# HV_PDU.net
KiCad netlist of a schematic drawn in Altium Designer
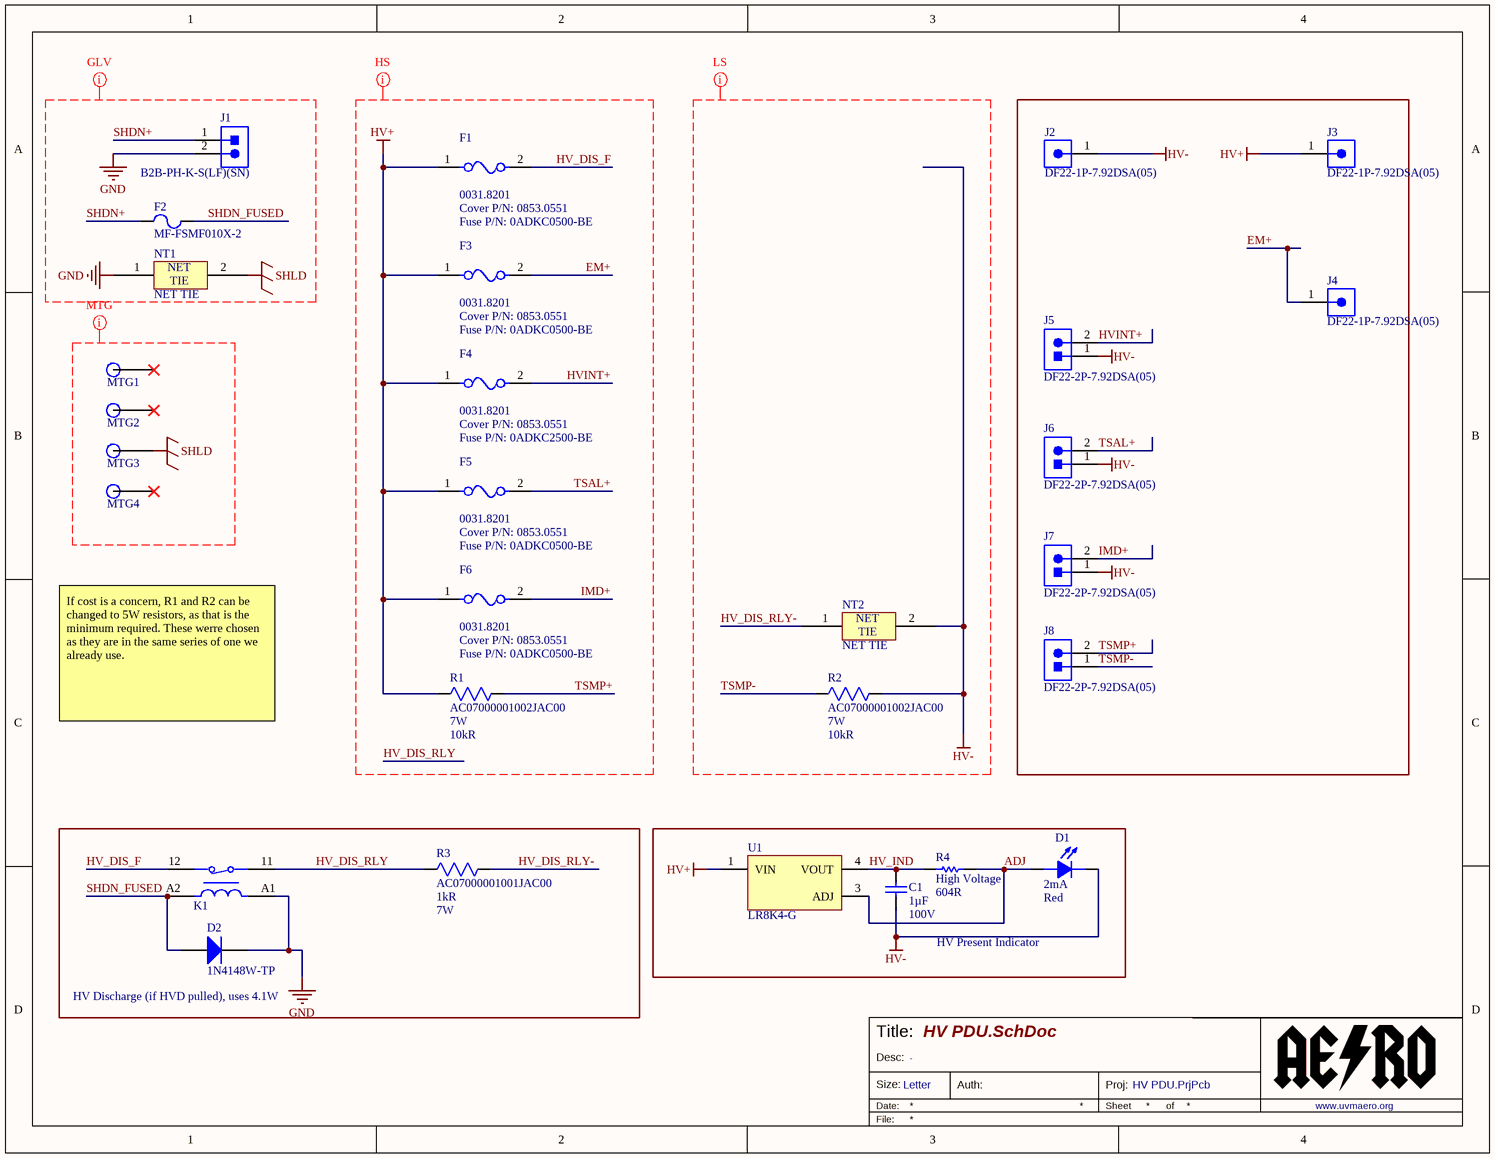
[diagram p0: HV PDU.SchDoc]

(export (version "E")
  (design (tool "Eeschema 10.0.6"))
  (components
    (comp (ref "C1")
      (value "C2012X7S2A105K125AB")
      (footprint "CAPC2013X145X20ML20")
      (description "Chip Capacitor, 1 uF, +/- 10%, 100 V, -55 to 125 degC, 0805 (2012 Metric), RoHS, Tape and Reel")
      (fields
        (field (name "PCN PART NUMBER") "MLCCPartNumberChange30/Nov/2012")
        (field (name "MANUFACTURER") "TDK")
        (field (name "CAPACITANCE") "1µF")
        (field (name "VOLTAGE - RATED") "100V")
      )
      (libsource (lib "AERO Parts") (part "C2012X7S2A105K125AB"))
    )
    (comp (ref "D1")
      (value "WP7113LSECK/J3")
      (footprint "LED_5MM")
      (description "Red 625nm LED Indication - Discrete 1.8V Radial")
      (fields
        (field (name "MANUFACTURER") "Kingbright")
        (field (name "TEST CURRENT") "2mA")
        (field (name "COLOR") "Red")
      )
      (libsource (lib "AERO Parts") (part "WP7113LSECK/J3"))
    )
    (comp (ref "D2")
      (value "1N4148W-TP")
      (footprint "MCC-SOD123_V")
      (description "High Speed Switching Diode, 400 mW, 150 mA, -65 to 150 degC, 2-Pin SOD123, RoHS, Tape and Reel")
      (fields (field (name "MANUFACTURER") "Micro Commercial Components"))
      (libsource (lib "Altium Content Vault") (part "D-AK-2"))
    )
    (comp (ref "F1")
      (value "0031.8201")
      (footprint "Schurter_0031.8201_ASM")
      (description "Fuse Block 10A 500V 1 Circuit Cartridge Through Hole")
      (fields
        (field (name "MANUFACTURER") "Schurter")
        (field (name "MANUFACTURER PART NUMBER") "00318201")
        (field (name "COVER P/N") "0853.0551")
        (field (name "FUSE P/N") "0ADKC0500-BE")
      )
      (libsource (lib "AERO Parts") (part "0031.8201"))
    )
    (comp (ref "F2")
      (value "MF-FSMF010X-2")
      (footprint "MF-FSMF")
      (description "Polymeric PTC Resettable Fuse 15V 100mA Ih Surface Mount 0603 (1608 Metric), Concave")
      (libsource (lib "AERO Parts") (part "MF-FSMF010X-2"))
    )
    (comp (ref "F3")
      (value "0031.8201")
      (footprint "Schurter_0031.8201_ASM")
      (description "Fuse Block 10A 500V 1 Circuit Cartridge Through Hole")
      (fields
        (field (name "MANUFACTURER") "Schurter")
        (field (name "MANUFACTURER PART NUMBER") "00318201")
        (field (name "COVER P/N") "0853.0551")
        (field (name "FUSE P/N") "0ADKC0500-BE")
      )
      (libsource (lib "AERO Parts") (part "0031.8201"))
    )
    (comp (ref "F4")
      (value "0031.8201")
      (footprint "Schurter_0031.8201_ASM")
      (description "Fuse Block 10A 500V 1 Circuit Cartridge Through Hole")
      (fields
        (field (name "MANUFACTURER") "Schurter")
        (field (name "MANUFACTURER PART NUMBER") "00318201")
        (field (name "COVER P/N") "0853.0551")
        (field (name "FUSE P/N") "0ADKC2500-BE")
      )
      (libsource (lib "AERO Parts") (part "0031.8201"))
    )
    (comp (ref "F5")
      (value "0031.8201")
      (footprint "Schurter_0031.8201_ASM")
      (description "Fuse Block 10A 500V 1 Circuit Cartridge Through Hole")
      (fields
        (field (name "MANUFACTURER") "Schurter")
        (field (name "MANUFACTURER PART NUMBER") "00318201")
        (field (name "COVER P/N") "0853.0551")
        (field (name "FUSE P/N") "0ADKC0500-BE")
      )
      (libsource (lib "AERO Parts") (part "0031.8201"))
    )
    (comp (ref "F6")
      (value "0031.8201")
      (footprint "Schurter_0031.8201_ASM")
      (description "Fuse Block 10A 500V 1 Circuit Cartridge Through Hole")
      (fields
        (field (name "MANUFACTURER") "Schurter")
        (field (name "MANUFACTURER PART NUMBER") "00318201")
        (field (name "COVER P/N") "0853.0551")
        (field (name "FUSE P/N") "0ADKC0500-BE")
      )
      (libsource (lib "AERO Parts") (part "0031.8201"))
    )
    (comp (ref "J1")
      (value "B2B-PH-K-S(LF)(SN)")
      (footprint "JST_Sales_America_Inc._B2B-PH-K-S_LF_SN_0")
      (description "Connector Header Through Hole 2 position 0.079\" (2.00mm)")
      (fields (field (name "MANUFACTURER") "JST") (field (name "MANUFACTURER PART NUMBER") "B2BPHKSLFSN"))
      (libsource (lib "AERO Parts") (part "B2B-PH-K-S(LF)(SN)"))
    )
    (comp (ref "J2")
      (value "DF22-1P-7.92DSA(05)")
      (footprint "DF22-1P-7.92DSA(05)")
      (description "Connector Header Through Hole 1 position")
      (fields (field (name "MANUFACTURER") "Hirose"))
      (libsource (lib "AERO Parts") (part "DF22-1P-7.92DSA(05)"))
    )
    (comp (ref "J3")
      (value "DF22-1P-7.92DSA(05)")
      (footprint "DF22-1P-7.92DSA(05)")
      (description "Connector Header Through Hole 1 position")
      (fields (field (name "MANUFACTURER") "Hirose"))
      (libsource (lib "") (part "DF22-1P-7.92DSA(05)_1"))
    )
    (comp (ref "J4")
      (value "DF22-1P-7.92DSA(05)")
      (footprint "DF22-1P-7.92DSA(05)")
      (description "Connector Header Through Hole 1 position")
      (fields (field (name "MANUFACTURER") "Hirose"))
      (libsource (lib "") (part "DF22-1P-7.92DSA(05)_1"))
    )
    (comp (ref "J5")
      (value "DF22-2P-7.92DSA(05)")
      (footprint "DF22-2P-7.92DSA_05_0")
      (description "Connector Header Through Hole 2 position 0.312\" (7.92mm)")
      (fields (field (name "MANUFACTURER") "Hirose"))
      (libsource (lib "AERO Parts") (part "DF22-2P-7.92DSA(05)"))
    )
    (comp (ref "J6")
      (value "DF22-2P-7.92DSA(05)")
      (footprint "DF22-2P-7.92DSA_05_0")
      (description "Connector Header Through Hole 2 position 0.312\" (7.92mm)")
      (fields (field (name "MANUFACTURER") "Hirose"))
      (libsource (lib "AERO Parts") (part "DF22-2P-7.92DSA(05)"))
    )
    (comp (ref "J7")
      (value "DF22-2P-7.92DSA(05)")
      (footprint "DF22-2P-7.92DSA_05_0")
      (description "Connector Header Through Hole 2 position 0.312\" (7.92mm)")
      (fields (field (name "MANUFACTURER") "Hirose"))
      (libsource (lib "AERO Parts") (part "DF22-2P-7.92DSA(05)"))
    )
    (comp (ref "J8")
      (value "DF22-2P-7.92DSA(05)")
      (footprint "DF22-2P-7.92DSA_05_0")
      (description "Connector Header Through Hole 2 position 0.312\" (7.92mm)")
      (fields (field (name "MANUFACTURER") "Hirose"))
      (libsource (lib "AERO Parts") (part "DF22-2P-7.92DSA(05)"))
    )
    (comp (ref "K1")
      (value "1393225-5")
      (footprint "RY553012")
      (description "General Purpose Relay SPST-NC (1 Form B) 12VDC Coil Through Hole")
      (fields (field (name "MANUFACTURER") "TE Connectivity"))
      (libsource (lib "AERO Parts") (part "1393225-5"))
    )
    (comp (ref "MTG1")
      (value "PCB MTG M3 HV")
      (footprint "MTG-M3-HV")
      (description "PCB Mounting for M3 Screw - HV")
      (libsource (lib "Hardware") (part "MTG"))
    )
    (comp (ref "MTG2")
      (value "PCB MTG M3 HV")
      (footprint "MTG-M3-HV")
      (description "PCB Mounting for M3 Screw - HV")
      (libsource (lib "Hardware") (part "MTG"))
    )
    (comp (ref "MTG3")
      (value "PCB MTG M3")
      (footprint "MTG-M3")
      (description "PCB Mounting for M3 Screw")
      (libsource (lib "Hardware") (part "MTG"))
    )
    (comp (ref "MTG4")
      (value "PCB MTG M3 HV")
      (footprint "MTG-M3-HV")
      (description "PCB Mounting for M3 Screw - HV")
      (libsource (lib "Hardware") (part "MTG"))
    )
    (comp (ref "NT1")
      (value "NET TIE")
      (footprint "20MIL_TIE")
      (description "Net Tie (No BOM)")
      (libsource (lib "AERO Parts") (part "NET TIE"))
    )
    (comp (ref "NT2")
      (value "NET TIE")
      (footprint "60MIL_TIE")
      (description "Net Tie (No BOM)")
      (libsource (lib "AERO Parts") (part "NET TIE"))
    )
    (comp (ref "R1")
      (value "AC07000001002JAC00")
      (footprint "AC07")
      (fields
        (field (name "MANUFACTURER") "Vishay BCcomponents")
        (field (name "TOLERANCE") "5%")
        (field (name "POWER RATING") "7W")
        (field (name "RESISTANCE") "10kR")
      )
      (libsource (lib "AERO Parts") (part "AC07000001002JAC00"))
    )
    (comp (ref "R2")
      (value "AC07000001002JAC00")
      (footprint "AC07")
      (fields
        (field (name "MANUFACTURER") "Vishay BCcomponents")
        (field (name "TOLERANCE") "5%")
        (field (name "POWER RATING") "7W")
        (field (name "RESISTANCE") "10kR")
      )
      (libsource (lib "AERO Parts") (part "AC07000001002JAC00"))
    )
    (comp (ref "R3")
      (value "AC07000001001JAC00")
      (footprint "AC07")
      (fields
        (field (name "MANUFACTURER") "Vishay BCcomponents")
        (field (name "TOLERANCE") "5%")
        (field (name "RESISTANCE") "1kR")
        (field (name "POWER RATING") "7W")
      )
      (libsource (lib "AERO Parts") (part "AC07000001001JAC00"))
    )
    (comp (ref "R4")
      (value "KTR10EZPF6040")
      (footprint "RESC2012X06N_HV")
      (fields
        (field (name "MANUFACTURER") "Rohm")
        (field (name "TOLERANCE") "1%")
        (field (name "HIGH VOLTAGE") "High Voltage")
        (field (name "RESISTANCE") "604R")
      )
      (libsource (lib "AERO Parts") (part "KTR10EZPF6040"))
    )
    (comp (ref "U1")
      (value "LR8K4-G")
      (footprint "Microchip_C04-189_MFG")
      (description "Linear Voltage Regulator IC Positive Adjustable 1 Output  10mA TO-252, (D-Pak)")
      (libsource (lib "AERO Parts") (part "LR8K4-G"))
    )
  )
  (nets
    (net (code "1") (name "/ADJ") (class "Default")
      (node (ref "D1") (pin "A") (pinfunction "A_A") (pintype "passive"))
      (node (ref "R4") (pin "2") (pinfunction "2_2") (pintype "passive"))
      (node (ref "U1") (pin "3") (pinfunction "ADJ_3") (pintype "passive"))
    )
    (net (code "2") (name "/EM+") (class "Default")
      (node (ref "F3") (pin "2") (pinfunction "2_2") (pintype "passive"))
      (node (ref "J4") (pin "1") (pinfunction "1_1") (pintype "passive"))
    )
    (net (code "3") (name "/HVINT+") (class "Default")
      (node (ref "F4") (pin "2") (pinfunction "2_2") (pintype "passive"))
      (node (ref "J5") (pin "2") (pinfunction "2_2") (pintype "passive"))
    )
    (net (code "4") (name "/HV_DIS_F") (class "Default")
      (node (ref "F1") (pin "2") (pinfunction "2_2") (pintype "passive"))
      (node (ref "K1") (pin "12") (pinfunction "12_12") (pintype "passive"))
    )
    (net (code "5") (name "/HV_DIS_RLY") (class "Default")
      (node (ref "K1") (pin "11") (pinfunction "11_11") (pintype "passive"))
      (node (ref "R3") (pin "1") (pinfunction "1_1") (pintype "passive"))
    )
    (net (code "6") (name "/HV_DIS_RLY-") (class "Default")
      (node (ref "NT2") (pin "1") (pintype "passive"))
      (node (ref "R3") (pin "2") (pinfunction "2_2") (pintype "passive"))
    )
    (net (code "7") (name "/HV_IND") (class "Default")
      (node (ref "C1") (pin "2") (pinfunction "2_2") (pintype "passive"))
      (node (ref "R4") (pin "1") (pinfunction "1_1") (pintype "passive"))
      (node (ref "U1") (pin "4") (pinfunction "VOUT_4") (pintype "power_in"))
    )
    (net (code "8") (name "/IMD+") (class "Default")
      (node (ref "F6") (pin "2") (pinfunction "2_2") (pintype "passive"))
      (node (ref "J7") (pin "2") (pinfunction "2_2") (pintype "passive"))
    )
    (net (code "9") (name "/SHDN+") (class "Default")
      (node (ref "F2") (pin "1") (pinfunction "1_1") (pintype "passive"))
      (node (ref "J1") (pin "1") (pinfunction "1_1") (pintype "passive"))
    )
    (net (code "10") (name "/SHDN_FUSED") (class "Default")
      (node (ref "D2") (pin "1") (pinfunction "A_1") (pintype "passive"))
      (node (ref "F2") (pin "2") (pinfunction "2_2") (pintype "passive"))
      (node (ref "K1") (pin "A2") (pinfunction "A2_A2") (pintype "passive"))
    )
    (net (code "11") (name "/TSAL+") (class "Default")
      (node (ref "F5") (pin "2") (pinfunction "2_2") (pintype "passive"))
      (node (ref "J6") (pin "2") (pinfunction "2_2") (pintype "passive"))
    )
    (net (code "12") (name "/TSMP+") (class "Default")
      (node (ref "J8") (pin "2") (pinfunction "2_2") (pintype "passive"))
      (node (ref "R1") (pin "2") (pinfunction "2_2") (pintype "passive"))
    )
    (net (code "13") (name "/TSMP-") (class "Default")
      (node (ref "J8") (pin "1") (pinfunction "1_1") (pintype "passive"))
      (node (ref "R2") (pin "1") (pinfunction "1_1") (pintype "passive"))
    )
    (net (code "14") (name "GND") (class "Default")
      (node (ref "D2") (pin "2") (pinfunction "K_2") (pintype "passive"))
      (node (ref "J1") (pin "2") (pinfunction "2_2") (pintype "passive"))
      (node (ref "K1") (pin "A1") (pinfunction "A1_A1") (pintype "passive"))
      (node (ref "NT1") (pin "1") (pintype "passive"))
    )
    (net (code "15") (name "HV+") (class "Default")
      (node (ref "F1") (pin "1") (pinfunction "1_1") (pintype "passive"))
      (node (ref "F3") (pin "1") (pinfunction "1_1") (pintype "passive"))
      (node (ref "F4") (pin "1") (pinfunction "1_1") (pintype "passive"))
      (node (ref "F5") (pin "1") (pinfunction "1_1") (pintype "passive"))
      (node (ref "F6") (pin "1") (pinfunction "1_1") (pintype "passive"))
      (node (ref "J3") (pin "1") (pinfunction "1_1") (pintype "passive"))
      (node (ref "R1") (pin "1") (pinfunction "1_1") (pintype "passive"))
      (node (ref "U1") (pin "1") (pinfunction "VIN_1") (pintype "power_in"))
    )
    (net (code "16") (name "HV-") (class "Default")
      (node (ref "C1") (pin "1") (pinfunction "1_1") (pintype "passive"))
      (node (ref "D1") (pin "K") (pinfunction "K_K") (pintype "passive"))
      (node (ref "J2") (pin "1") (pinfunction "1_1") (pintype "passive"))
      (node (ref "J5") (pin "1") (pinfunction "1_1") (pintype "passive"))
      (node (ref "J6") (pin "1") (pinfunction "1_1") (pintype "passive"))
      (node (ref "J7") (pin "1") (pinfunction "1_1") (pintype "passive"))
      (node (ref "NT2") (pin "2") (pintype "passive"))
      (node (ref "R2") (pin "2") (pinfunction "2_2") (pintype "passive"))
    )
    (net (code "17") (name "SHLD") (class "Default")
      (node (ref "MTG3") (pin "1") (pinfunction "1_1") (pintype "passive"))
      (node (ref "NT1") (pin "2") (pintype "passive"))
    )
    (net (code "18") (name "unconnected-(MTG1-Pad1)") (class "Default")
      (node (ref "MTG1") (pin "1") (pinfunction "1_1") (pintype "passive+no_connect"))
    )
    (net (code "19") (name "unconnected-(MTG2-Pad1)") (class "Default")
      (node (ref "MTG2") (pin "1") (pinfunction "1_1") (pintype "passive+no_connect"))
    )
    (net (code "20") (name "unconnected-(MTG4-Pad1)") (class "Default")
      (node (ref "MTG4") (pin "1") (pinfunction "1_1") (pintype "passive+no_connect"))
    )
  )
)
